# Mach_trai_tim.net
KiCad netlist of a schematic drawn in Altium Designer
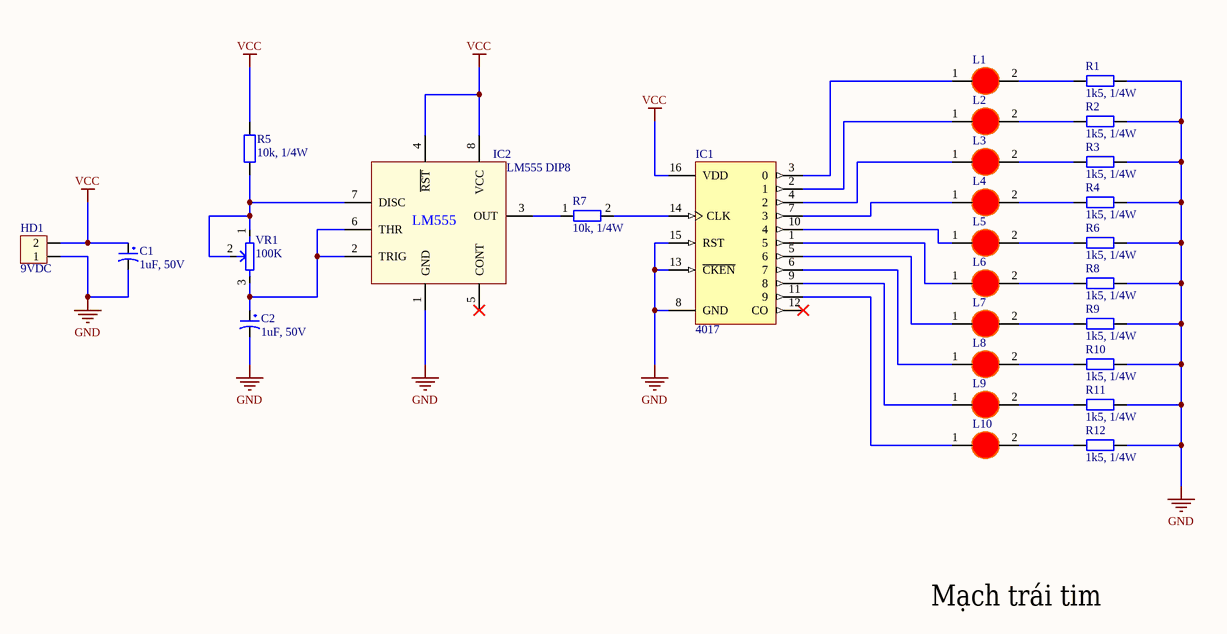
[diagram p0: Mach trai tim.SchDoc]

(export (version "E")
  (design (tool "Eeschema 10.0.6"))
  (components
    (comp (ref "C1")
      (value "1uF, 50V")
      (footprint "tu hoa 5mm")
      (description "Cắm")
      (libsource (lib "Tu dien") (part "Tu Hoa 1uF 50V 5x11"))
    )
    (comp (ref "C2")
      (value "1uF, 50V")
      (footprint "tu hoa 5mm")
      (description "Cắm")
      (libsource (lib "Tu dien") (part "Tu Hoa 1uF 50V 5x11"))
    )
    (comp (ref "HD1")
      (value "9VDC")
      (footprint "HED2")
      (description "Header 2 (Green)")
      (libsource (lib "syhaunguyen") (part "Hed2"))
    )
    (comp (ref "IC1")
      (value "4017")
      (footprint "DIP16/W0.3")
      (description "Decade Counter/Divider with 10 Decoded Outputs")
      (fields (field (name "DESIGNED BY") "VanDungEvn"))
      (libsource (lib "syhaunguyen") (part "4017"))
    )
    (comp (ref "IC2") (value "LM555 DIP8") (footprint "LM555") (libsource (lib "TV NQM") (part "LM555")))
    (comp (ref "L1")
      (value "LED 5mm")
      (footprint "LED-5MM-RED")
      (description "Cắm")
      (libsource (lib "Led") (part "LED 5mm Do"))
    )
    (comp (ref "L2")
      (value "LED 5mm")
      (footprint "LED-5MM-RED")
      (description "Cắm")
      (libsource (lib "Led") (part "LED 5mm Do"))
    )
    (comp (ref "L3")
      (value "LED 5mm")
      (footprint "LED-5MM-RED")
      (description "Cắm")
      (libsource (lib "Led") (part "LED 5mm Do"))
    )
    (comp (ref "L4")
      (value "LED 5mm")
      (footprint "LED-5MM-RED")
      (description "Cắm")
      (libsource (lib "Led") (part "LED 5mm Do"))
    )
    (comp (ref "L5")
      (value "LED 5mm")
      (footprint "LED-5MM-RED")
      (description "Cắm")
      (libsource (lib "Led") (part "LED 5mm Do"))
    )
    (comp (ref "L6")
      (value "LED 5mm")
      (footprint "LED-5MM-RED")
      (description "Cắm")
      (libsource (lib "Led") (part "LED 5mm Do"))
    )
    (comp (ref "L7")
      (value "LED 5mm")
      (footprint "LED-5MM-RED")
      (description "Cắm")
      (libsource (lib "Led") (part "LED 5mm Do"))
    )
    (comp (ref "L8")
      (value "LED 5mm")
      (footprint "LED-5MM-RED")
      (description "Cắm")
      (libsource (lib "Led") (part "LED 5mm Do"))
    )
    (comp (ref "L9")
      (value "LED 5mm")
      (footprint "LED-5MM-RED")
      (description "Cắm")
      (libsource (lib "Led") (part "LED 5mm Do"))
    )
    (comp (ref "L10")
      (value "LED 5mm")
      (footprint "LED-5MM-RED")
      (description "Cắm")
      (libsource (lib "Led") (part "LED 5mm Do"))
    )
    (comp (ref "R1")
      (value "1k5, 1/4W")
      (footprint "tro vach 1/4w")
      (description "Cắm")
      (libsource (lib "Dien Tro") (part "Tro Vach 1/4W 5% 1k"))
    )
    (comp (ref "R2")
      (value "1k5, 1/4W")
      (footprint "tro vach 1/4w")
      (description "Cắm")
      (libsource (lib "Dien Tro") (part "Tro Vach 1/4W 5% 1k"))
    )
    (comp (ref "R3")
      (value "1k5, 1/4W")
      (footprint "tro vach 1/4w")
      (description "Cắm")
      (libsource (lib "Dien Tro") (part "Tro Vach 1/4W 5% 1k"))
    )
    (comp (ref "R4")
      (value "1k5, 1/4W")
      (footprint "tro vach 1/4w")
      (description "Cắm")
      (libsource (lib "Dien Tro") (part "Tro Vach 1/4W 5% 1k"))
    )
    (comp (ref "R5")
      (value "10k, 1/4W")
      (footprint "R1/4W")
      (description "Resistor 1/4W")
      (libsource (lib "") (part "R1/4W_1"))
    )
    (comp (ref "R6")
      (value "1k5, 1/4W")
      (footprint "tro vach 1/4w")
      (description "Cắm")
      (libsource (lib "Dien Tro") (part "Tro Vach 1/4W 5% 1k"))
    )
    (comp (ref "R7")
      (value "10k, 1/4W")
      (footprint "R1/4W")
      (description "Resistor 1/4W")
      (libsource (lib "syhaunguyen") (part "R1/4W"))
    )
    (comp (ref "R8")
      (value "1k5, 1/4W")
      (footprint "tro vach 1/4w")
      (description "Cắm")
      (libsource (lib "Dien Tro") (part "Tro Vach 1/4W 5% 1k"))
    )
    (comp (ref "R9")
      (value "1k5, 1/4W")
      (footprint "tro vach 1/4w")
      (description "Cắm")
      (libsource (lib "Dien Tro") (part "Tro Vach 1/4W 5% 1k"))
    )
    (comp (ref "R10")
      (value "1k5, 1/4W")
      (footprint "tro vach 1/4w")
      (description "Cắm")
      (libsource (lib "Dien Tro") (part "Tro Vach 1/4W 5% 1k"))
    )
    (comp (ref "R11")
      (value "1k5, 1/4W")
      (footprint "tro vach 1/4w")
      (description "Cắm")
      (libsource (lib "Dien Tro") (part "Tro Vach 1/4W 5% 1k"))
    )
    (comp (ref "R12")
      (value "1k5, 1/4W")
      (footprint "tro vach 1/4w")
      (description "Cắm")
      (libsource (lib "Dien Tro") (part "Tro Vach 1/4W 5% 1k"))
    )
    (comp (ref "VR1")
      (value "100K")
      (footprint "Bien Tro Tam Giac Dung")
      (description "Cắm")
      (libsource (lib "Dien Tro") (part "Bien tro tam giac 100K Dung"))
    )
  )
  (nets
    (net (code "1") (name "GND") (class "Default")
      (node (ref "C1") (pin "2") (pinfunction "2_2") (pintype "passive"))
      (node (ref "C2") (pin "2") (pinfunction "2_2") (pintype "passive"))
      (node (ref "HD1") (pin "1") (pinfunction "1_1") (pintype "passive"))
      (node (ref "IC1") (pin "13") (pinfunction "~{CKEN}_13") (pintype "input"))
      (node (ref "IC1") (pin "15") (pinfunction "RST_15") (pintype "input"))
      (node (ref "IC1") (pin "8") (pinfunction "GND_8") (pintype "power_in"))
      (node (ref "IC2") (pin "1") (pinfunction "GND_1") (pintype "passive"))
      (node (ref "R1") (pin "2") (pinfunction "2_2") (pintype "passive"))
      (node (ref "R10") (pin "2") (pinfunction "2_2") (pintype "passive"))
      (node (ref "R11") (pin "2") (pinfunction "2_2") (pintype "passive"))
      (node (ref "R12") (pin "2") (pinfunction "2_2") (pintype "passive"))
      (node (ref "R2") (pin "2") (pinfunction "2_2") (pintype "passive"))
      (node (ref "R3") (pin "2") (pinfunction "2_2") (pintype "passive"))
      (node (ref "R4") (pin "2") (pinfunction "2_2") (pintype "passive"))
      (node (ref "R6") (pin "2") (pinfunction "2_2") (pintype "passive"))
      (node (ref "R8") (pin "2") (pinfunction "2_2") (pintype "passive"))
      (node (ref "R9") (pin "2") (pinfunction "2_2") (pintype "passive"))
    )
    (net (code "2") (name "Net-(IC1-0)") (class "Default")
      (node (ref "IC1") (pin "3") (pinfunction "0_3") (pintype "output"))
      (node (ref "L1") (pin "1") (pinfunction "A_1") (pintype "passive"))
    )
    (net (code "3") (name "Net-(IC1-1)") (class "Default")
      (node (ref "IC1") (pin "2") (pinfunction "1_2") (pintype "output"))
      (node (ref "L2") (pin "1") (pinfunction "A_1") (pintype "passive"))
    )
    (net (code "4") (name "Net-(IC1-2)") (class "Default")
      (node (ref "IC1") (pin "4") (pinfunction "2_4") (pintype "output"))
      (node (ref "L3") (pin "1") (pinfunction "A_1") (pintype "passive"))
    )
    (net (code "5") (name "Net-(IC1-3)") (class "Default")
      (node (ref "IC1") (pin "7") (pinfunction "3_7") (pintype "output"))
      (node (ref "L4") (pin "1") (pinfunction "A_1") (pintype "passive"))
    )
    (net (code "6") (name "Net-(IC1-4)") (class "Default")
      (node (ref "IC1") (pin "10") (pinfunction "4_10") (pintype "output"))
      (node (ref "L5") (pin "1") (pinfunction "A_1") (pintype "passive"))
    )
    (net (code "7") (name "Net-(IC1-5)") (class "Default")
      (node (ref "IC1") (pin "1") (pinfunction "5_1") (pintype "output"))
      (node (ref "L6") (pin "1") (pinfunction "A_1") (pintype "passive"))
    )
    (net (code "8") (name "Net-(IC1-6)") (class "Default")
      (node (ref "IC1") (pin "5") (pinfunction "6_5") (pintype "output"))
      (node (ref "L7") (pin "1") (pinfunction "A_1") (pintype "passive"))
    )
    (net (code "9") (name "Net-(IC1-7)") (class "Default")
      (node (ref "IC1") (pin "6") (pinfunction "7_6") (pintype "output"))
      (node (ref "L8") (pin "1") (pinfunction "A_1") (pintype "passive"))
    )
    (net (code "10") (name "Net-(IC1-8)") (class "Default")
      (node (ref "IC1") (pin "9") (pinfunction "8_9") (pintype "output"))
      (node (ref "L9") (pin "1") (pinfunction "A_1") (pintype "passive"))
    )
    (net (code "11") (name "Net-(IC1-9)") (class "Default")
      (node (ref "IC1") (pin "11") (pinfunction "9_11") (pintype "output"))
      (node (ref "L10") (pin "1") (pinfunction "A_1") (pintype "passive"))
    )
    (net (code "12") (name "Net-(IC1-CLK)") (class "Default")
      (node (ref "IC1") (pin "14") (pinfunction "CLK_14") (pintype "input"))
      (node (ref "R7") (pin "2") (pinfunction "2_2") (pintype "passive"))
    )
    (net (code "13") (name "Net-(IC2-DISC)") (class "Default")
      (node (ref "IC2") (pin "7") (pinfunction "DISC_7") (pintype "passive"))
      (node (ref "R5") (pin "2") (pinfunction "2_2") (pintype "passive"))
      (node (ref "VR1") (pin "1") (pinfunction "1_1") (pintype "passive"))
      (node (ref "VR1") (pin "2") (pinfunction "2_2") (pintype "passive"))
    )
    (net (code "14") (name "Net-(IC2-OUT)") (class "Default")
      (node (ref "IC2") (pin "3") (pinfunction "OUT_3") (pintype "passive"))
      (node (ref "R7") (pin "1") (pinfunction "1_1") (pintype "passive"))
    )
    (net (code "15") (name "Net-(IC2-THR)") (class "Default")
      (node (ref "C2") (pin "1") (pinfunction "1_1") (pintype "passive"))
      (node (ref "IC2") (pin "2") (pinfunction "TRIG_2") (pintype "passive"))
      (node (ref "IC2") (pin "6") (pinfunction "THR_6") (pintype "passive"))
      (node (ref "VR1") (pin "3") (pinfunction "3_3") (pintype "passive"))
    )
    (net (code "16") (name "Net-(L1-K)") (class "Default")
      (node (ref "L1") (pin "2") (pinfunction "K_2") (pintype "passive"))
      (node (ref "R1") (pin "1") (pinfunction "1_1") (pintype "passive"))
    )
    (net (code "17") (name "Net-(L2-K)") (class "Default")
      (node (ref "L2") (pin "2") (pinfunction "K_2") (pintype "passive"))
      (node (ref "R2") (pin "1") (pinfunction "1_1") (pintype "passive"))
    )
    (net (code "18") (name "Net-(L3-K)") (class "Default")
      (node (ref "L3") (pin "2") (pinfunction "K_2") (pintype "passive"))
      (node (ref "R3") (pin "1") (pinfunction "1_1") (pintype "passive"))
    )
    (net (code "19") (name "Net-(L4-K)") (class "Default")
      (node (ref "L4") (pin "2") (pinfunction "K_2") (pintype "passive"))
      (node (ref "R4") (pin "1") (pinfunction "1_1") (pintype "passive"))
    )
    (net (code "20") (name "Net-(L5-K)") (class "Default")
      (node (ref "L5") (pin "2") (pinfunction "K_2") (pintype "passive"))
      (node (ref "R6") (pin "1") (pinfunction "1_1") (pintype "passive"))
    )
    (net (code "21") (name "Net-(L6-K)") (class "Default")
      (node (ref "L6") (pin "2") (pinfunction "K_2") (pintype "passive"))
      (node (ref "R8") (pin "1") (pinfunction "1_1") (pintype "passive"))
    )
    (net (code "22") (name "Net-(L7-K)") (class "Default")
      (node (ref "L7") (pin "2") (pinfunction "K_2") (pintype "passive"))
      (node (ref "R9") (pin "1") (pinfunction "1_1") (pintype "passive"))
    )
    (net (code "23") (name "Net-(L8-K)") (class "Default")
      (node (ref "L8") (pin "2") (pinfunction "K_2") (pintype "passive"))
      (node (ref "R10") (pin "1") (pinfunction "1_1") (pintype "passive"))
    )
    (net (code "24") (name "Net-(L9-K)") (class "Default")
      (node (ref "L9") (pin "2") (pinfunction "K_2") (pintype "passive"))
      (node (ref "R11") (pin "1") (pinfunction "1_1") (pintype "passive"))
    )
    (net (code "25") (name "Net-(L10-K)") (class "Default")
      (node (ref "L10") (pin "2") (pinfunction "K_2") (pintype "passive"))
      (node (ref "R12") (pin "1") (pinfunction "1_1") (pintype "passive"))
    )
    (net (code "26") (name "VCC") (class "Default")
      (node (ref "C1") (pin "1") (pinfunction "1_1") (pintype "passive"))
      (node (ref "HD1") (pin "2") (pinfunction "2_2") (pintype "passive"))
      (node (ref "IC1") (pin "16") (pinfunction "VDD_16") (pintype "power_in"))
      (node (ref "IC2") (pin "4") (pinfunction "~{RST}_4") (pintype "passive"))
      (node (ref "IC2") (pin "8") (pinfunction "VCC_8") (pintype "passive"))
      (node (ref "R5") (pin "1") (pinfunction "1_1") (pintype "passive"))
    )
    (net (code "27") (name "unconnected-(IC1-CO-Pad12)") (class "Default")
      (node (ref "IC1") (pin "12") (pinfunction "CO_12") (pintype "output+no_connect"))
    )
    (net (code "28") (name "unconnected-(IC2-CONT-Pad5)") (class "Default")
      (node (ref "IC2") (pin "5") (pinfunction "CONT_5") (pintype "passive+no_connect"))
    )
  )
)
